# Drivers.net
KiCad netlist of a schematic drawn in Altium Designer
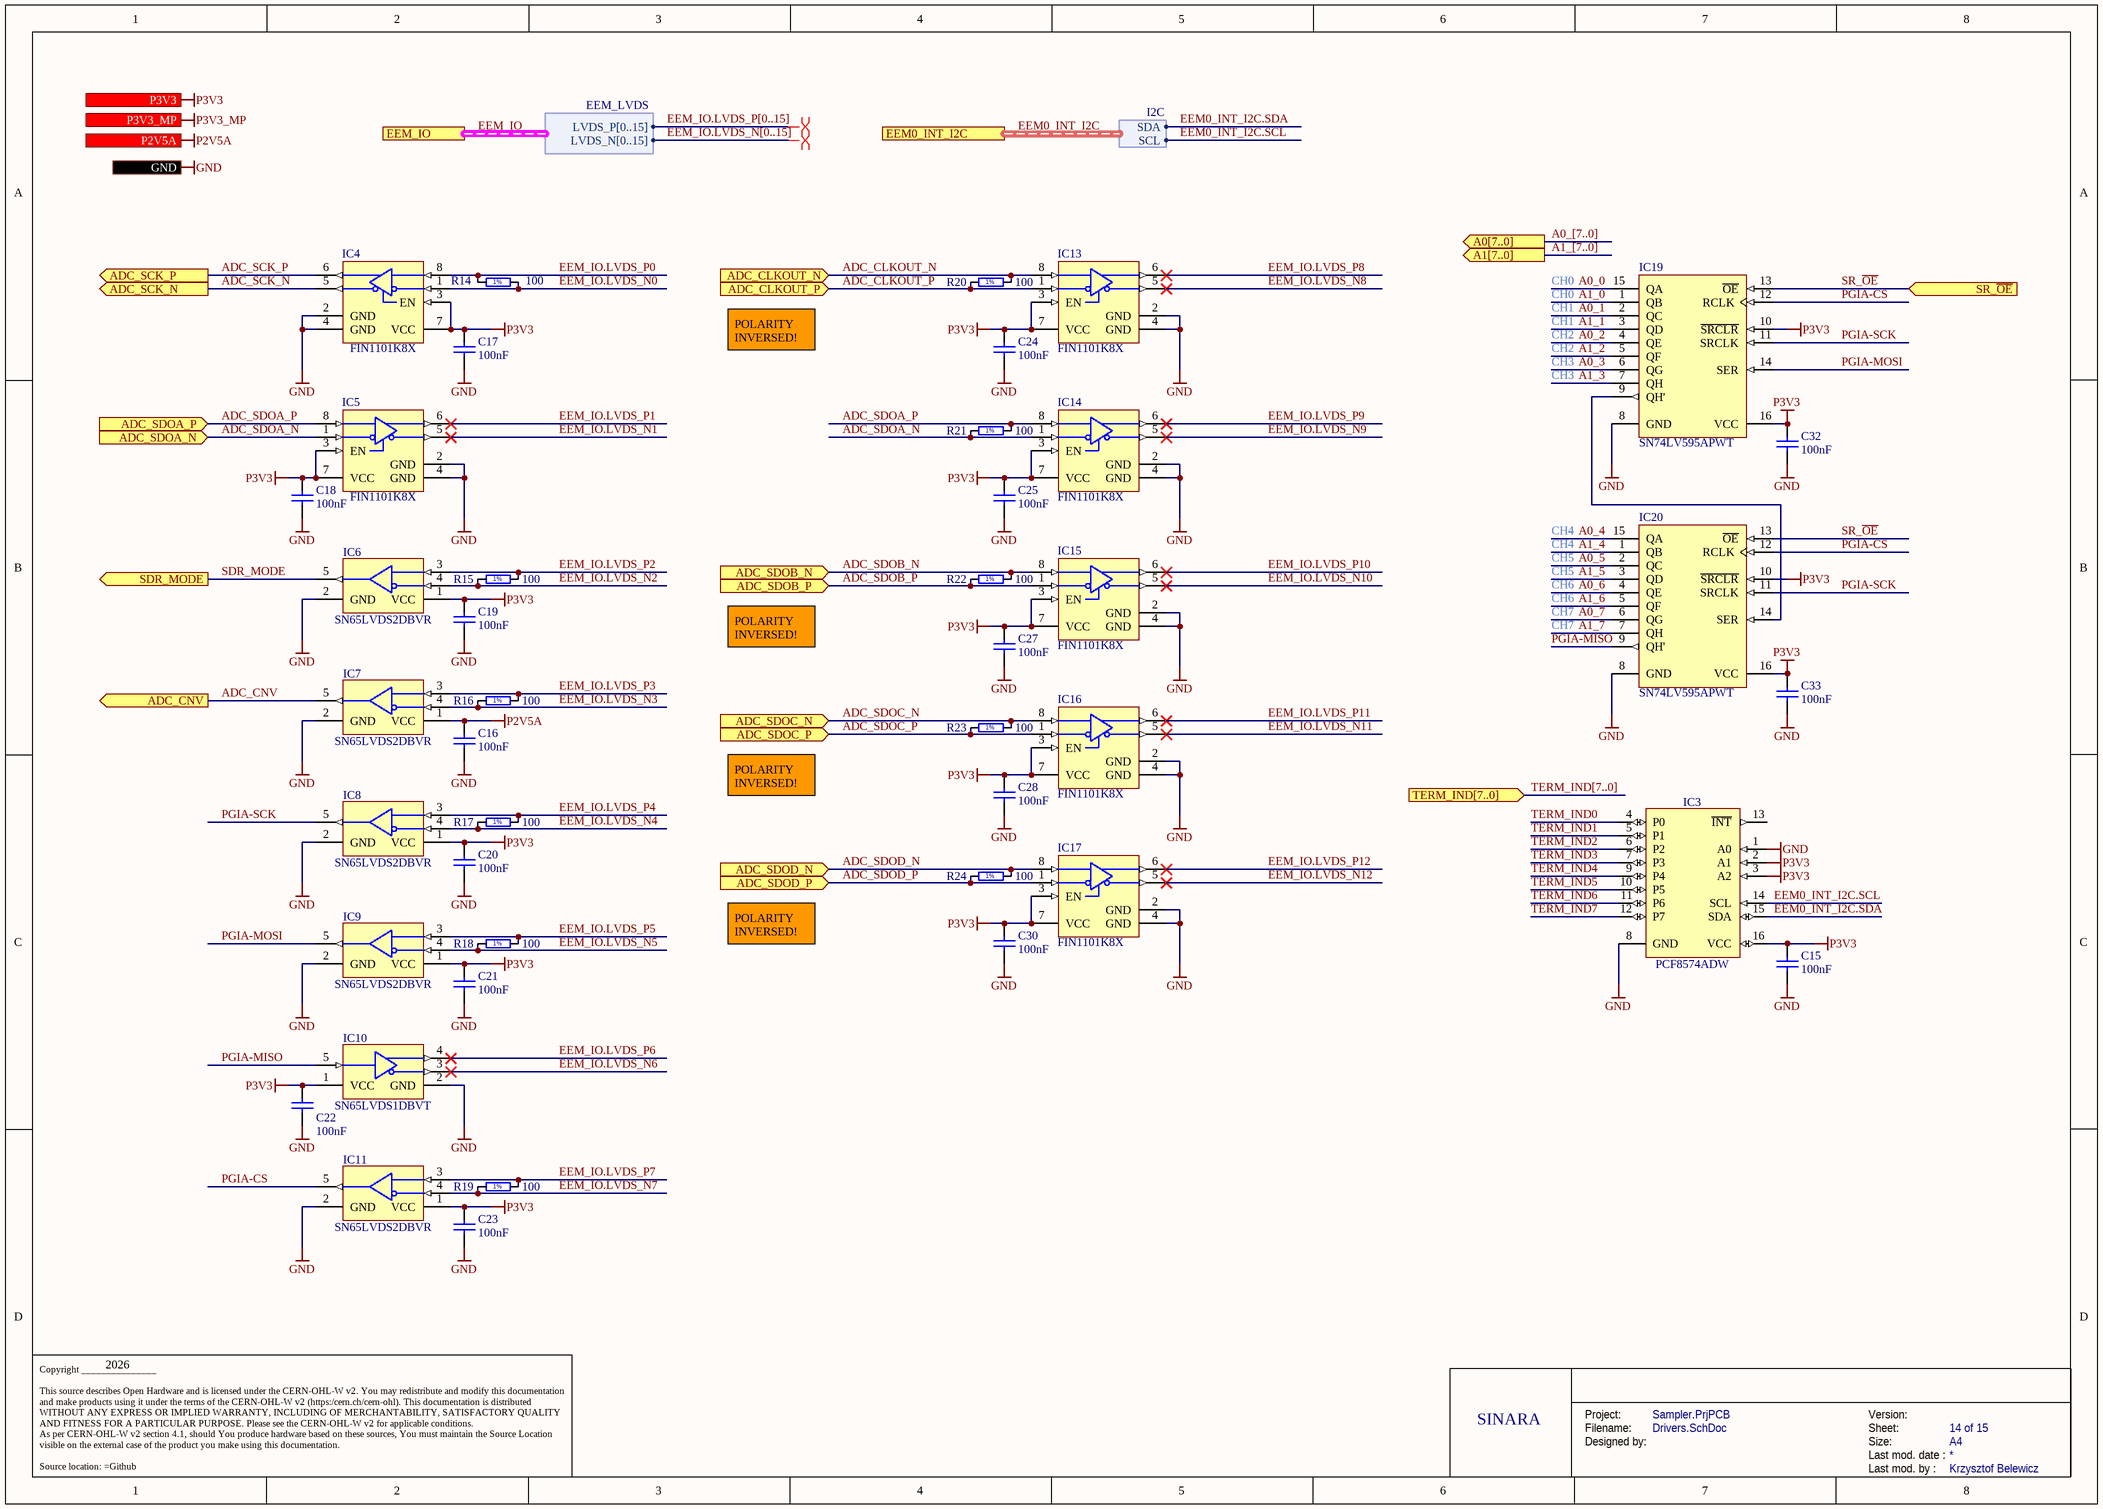
[diagram p0: Drivers.SchDoc]

(export (version "E")
  (design (tool "Eeschema 10.0.6"))
  (components
    (comp (ref "C15")
      (value "100nF")
      (footprint "CAPC1005X55N")
      (description "Non-polarised capacitor")
      (fields
        (field (name "PART NUMBER") "CC0402_100NF_50V_10%_X7R")
        (field (name "VOLTAGE") "50V")
        (field (name "AUTHOR") "CERN DEM MR")
      )
      (libsource (lib "Capacitors") (part "Capacitor - non polarized"))
    )
    (comp (ref "C16")
      (value "100nF")
      (footprint "CAPC1005X55N")
      (description "Non-polarised capacitor")
      (fields
        (field (name "PART NUMBER") "CC0402_100NF_50V_10%_X7R")
        (field (name "VOLTAGE") "50V")
        (field (name "AUTHOR") "CERN DEM MR")
      )
      (libsource (lib "Capacitors") (part "Capacitor - non polarized"))
    )
    (comp (ref "C17")
      (value "100nF")
      (footprint "CAPC1005X55N")
      (description "Non-polarised capacitor")
      (fields
        (field (name "PART NUMBER") "CC0402_100NF_50V_10%_X7R")
        (field (name "VOLTAGE") "50V")
        (field (name "AUTHOR") "CERN DEM MR")
      )
      (libsource (lib "Capacitors") (part "Capacitor - non polarized"))
    )
    (comp (ref "C18")
      (value "100nF")
      (footprint "CAPC1005X55N")
      (description "Non-polarised capacitor")
      (fields
        (field (name "PART NUMBER") "CC0402_100NF_50V_10%_X7R")
        (field (name "VOLTAGE") "50V")
        (field (name "AUTHOR") "CERN DEM MR")
      )
      (libsource (lib "Capacitors") (part "Capacitor - non polarized"))
    )
    (comp (ref "C19")
      (value "100nF")
      (footprint "CAPC1005X55N")
      (description "Non-polarised capacitor")
      (fields
        (field (name "PART NUMBER") "CC0402_100NF_50V_10%_X7R")
        (field (name "VOLTAGE") "50V")
        (field (name "AUTHOR") "CERN DEM MR")
      )
      (libsource (lib "Capacitors") (part "Capacitor - non polarized"))
    )
    (comp (ref "C20")
      (value "100nF")
      (footprint "CAPC1005X55N")
      (description "Non-polarised capacitor")
      (fields
        (field (name "PART NUMBER") "CC0402_100NF_50V_10%_X7R")
        (field (name "VOLTAGE") "50V")
        (field (name "AUTHOR") "CERN DEM MR")
      )
      (libsource (lib "Capacitors") (part "Capacitor - non polarized"))
    )
    (comp (ref "C21")
      (value "100nF")
      (footprint "CAPC1005X55N")
      (description "Non-polarised capacitor")
      (fields
        (field (name "PART NUMBER") "CC0402_100NF_50V_10%_X7R")
        (field (name "VOLTAGE") "50V")
        (field (name "AUTHOR") "CERN DEM MR")
      )
      (libsource (lib "Capacitors") (part "Capacitor - non polarized"))
    )
    (comp (ref "C22")
      (value "100nF")
      (footprint "CAPC1005X55N")
      (description "Non-polarised capacitor")
      (fields
        (field (name "PART NUMBER") "CC0402_100NF_50V_10%_X7R")
        (field (name "VOLTAGE") "50V")
        (field (name "AUTHOR") "CERN DEM MR")
      )
      (libsource (lib "Capacitors") (part "Capacitor - non polarized"))
    )
    (comp (ref "C23")
      (value "100nF")
      (footprint "CAPC1005X55N")
      (description "Non-polarised capacitor")
      (fields
        (field (name "PART NUMBER") "CC0402_100NF_50V_10%_X7R")
        (field (name "VOLTAGE") "50V")
        (field (name "AUTHOR") "CERN DEM MR")
      )
      (libsource (lib "Capacitors") (part "Capacitor - non polarized"))
    )
    (comp (ref "C24")
      (value "100nF")
      (footprint "CAPC1005X55N")
      (description "Non-polarised capacitor")
      (fields
        (field (name "PART NUMBER") "CC0402_100NF_50V_10%_X7R")
        (field (name "VOLTAGE") "50V")
        (field (name "AUTHOR") "CERN DEM MR")
      )
      (libsource (lib "Capacitors") (part "Capacitor - non polarized"))
    )
    (comp (ref "C25")
      (value "100nF")
      (footprint "CAPC1005X55N")
      (description "Non-polarised capacitor")
      (fields
        (field (name "PART NUMBER") "CC0402_100NF_50V_10%_X7R")
        (field (name "VOLTAGE") "50V")
        (field (name "AUTHOR") "CERN DEM MR")
      )
      (libsource (lib "Capacitors") (part "Capacitor - non polarized"))
    )
    (comp (ref "C27")
      (value "100nF")
      (footprint "CAPC1005X55N")
      (description "Non-polarised capacitor")
      (fields
        (field (name "PART NUMBER") "CC0402_100NF_50V_10%_X7R")
        (field (name "VOLTAGE") "50V")
        (field (name "AUTHOR") "CERN DEM MR")
      )
      (libsource (lib "Capacitors") (part "Capacitor - non polarized"))
    )
    (comp (ref "C28")
      (value "100nF")
      (footprint "CAPC1005X55N")
      (description "Non-polarised capacitor")
      (fields
        (field (name "PART NUMBER") "CC0402_100NF_50V_10%_X7R")
        (field (name "VOLTAGE") "50V")
        (field (name "AUTHOR") "CERN DEM MR")
      )
      (libsource (lib "Capacitors") (part "Capacitor - non polarized"))
    )
    (comp (ref "C30")
      (value "100nF")
      (footprint "CAPC1005X55N")
      (description "Non-polarised capacitor")
      (fields
        (field (name "PART NUMBER") "CC0402_100NF_50V_10%_X7R")
        (field (name "VOLTAGE") "50V")
        (field (name "AUTHOR") "CERN DEM MR")
      )
      (libsource (lib "Capacitors") (part "Capacitor - non polarized"))
    )
    (comp (ref "C32")
      (value "100nF")
      (footprint "CAPC1005X55N")
      (description "Non-polarised capacitor")
      (fields
        (field (name "PART NUMBER") "CC0402_100NF_50V_10%_X7R")
        (field (name "VOLTAGE") "50V")
        (field (name "AUTHOR") "CERN DEM MR")
      )
      (libsource (lib "Capacitors") (part "Capacitor - non polarized"))
    )
    (comp (ref "C33")
      (value "100nF")
      (footprint "CAPC1005X55N")
      (description "Non-polarised capacitor")
      (fields
        (field (name "PART NUMBER") "CC0402_100NF_50V_10%_X7R")
        (field (name "VOLTAGE") "50V")
        (field (name "AUTHOR") "CERN DEM MR")
      )
      (libsource (lib "Capacitors") (part "Capacitor - non polarized"))
    )
    (comp (ref "IC3")
      (value "PCF8574ADW")
      (footprint "SOIC127P1030X265-16N")
      (description "Remote 8-bit I/O Expander For I2C Bus")
      (fields (field (name "MANUFACTURER") "TEXAS INSTRUMENTS") (field (name "AUTHOR") "CERN DEM JLC"))
      (libsource (lib "ICs And Semiconductors") (part "PCF8574ADW"))
    )
    (comp (ref "IC4")
      (value "FIN1101K8X")
      (footprint "SOP50P310X90-8N")
      (description "LVDS Single Port High Speed Repeater")
      (fields (field (name "MANUFACTURER") "FAIRCHILD SEMICONDUCTOR") (field (name "AUTHOR") "CERN DEM JLC"))
      (libsource (lib "") (part "FIN1101K8X_1"))
    )
    (comp (ref "IC5")
      (value "FIN1101K8X")
      (footprint "SOP50P310X90-8N")
      (description "LVDS Single Port High Speed Repeater")
      (fields (field (name "MANUFACTURER") "FAIRCHILD SEMICONDUCTOR") (field (name "AUTHOR") "CERN DEM JLC"))
      (libsource (lib "ICs And Semiconductors") (part "FIN1101K8X"))
    )
    (comp (ref "IC6")
      (value "SN65LVDS2DBVR")
      (footprint "SOT95P280X145-5N")
      (description "High-Speed Differential Line Receiver")
      (fields (field (name "MANUFACTURER") "TEXAS INSTRUMENTS") (field (name "AUTHOR") "CERN DEM JLC"))
      (libsource (lib "ICs And Semiconductors") (part "SN65LVDS2DBV"))
    )
    (comp (ref "IC7")
      (value "SN65LVDS2DBVR")
      (footprint "SOT95P280X145-5N")
      (description "High-Speed Differential Line Receiver")
      (fields (field (name "MANUFACTURER") "TEXAS INSTRUMENTS") (field (name "AUTHOR") "CERN DEM JLC"))
      (libsource (lib "ICs And Semiconductors") (part "SN65LVDS2DBV"))
    )
    (comp (ref "IC8")
      (value "SN65LVDS2DBVR")
      (footprint "SOT95P280X145-5N")
      (description "High-Speed Differential Line Receiver")
      (fields (field (name "MANUFACTURER") "TEXAS INSTRUMENTS") (field (name "AUTHOR") "CERN DEM JLC"))
      (libsource (lib "ICs And Semiconductors") (part "SN65LVDS2DBV"))
    )
    (comp (ref "IC9")
      (value "SN65LVDS2DBVR")
      (footprint "SOT95P280X145-5N")
      (description "High-Speed Differential Line Receiver")
      (fields (field (name "MANUFACTURER") "TEXAS INSTRUMENTS") (field (name "AUTHOR") "CERN DEM JLC"))
      (libsource (lib "ICs And Semiconductors") (part "SN65LVDS2DBV"))
    )
    (comp (ref "IC10")
      (value "SN65LVDS1DBVT")
      (footprint "SOT95P280X145-5N")
      (description "High-Speed Differential Line Driver")
      (fields (field (name "MANUFACTURER") "TEXAS INSTRUMENTS") (field (name "AUTHOR") "CERN DEM JLC"))
      (libsource (lib "ICs And Semiconductors") (part "SN65LVDS1DBV"))
    )
    (comp (ref "IC11")
      (value "SN65LVDS2DBVR")
      (footprint "SOT95P280X145-5N")
      (description "High-Speed Differential Line Receiver")
      (fields (field (name "MANUFACTURER") "TEXAS INSTRUMENTS") (field (name "AUTHOR") "CERN DEM JLC"))
      (libsource (lib "ICs And Semiconductors") (part "SN65LVDS2DBV"))
    )
    (comp (ref "IC13")
      (value "FIN1101K8X")
      (footprint "SOP50P310X90-8N")
      (description "LVDS Single Port High Speed Repeater")
      (fields (field (name "MANUFACTURER") "FAIRCHILD SEMICONDUCTOR") (field (name "AUTHOR") "CERN DEM JLC"))
      (libsource (lib "ICs And Semiconductors") (part "FIN1101K8X"))
    )
    (comp (ref "IC14")
      (value "FIN1101K8X")
      (footprint "SOP50P310X90-8N")
      (description "LVDS Single Port High Speed Repeater")
      (fields (field (name "MANUFACTURER") "FAIRCHILD SEMICONDUCTOR") (field (name "AUTHOR") "CERN DEM JLC"))
      (libsource (lib "ICs And Semiconductors") (part "FIN1101K8X"))
    )
    (comp (ref "IC15")
      (value "FIN1101K8X")
      (footprint "SOP50P310X90-8N")
      (description "LVDS Single Port High Speed Repeater")
      (fields (field (name "MANUFACTURER") "FAIRCHILD SEMICONDUCTOR") (field (name "AUTHOR") "CERN DEM JLC"))
      (libsource (lib "ICs And Semiconductors") (part "FIN1101K8X"))
    )
    (comp (ref "IC16")
      (value "FIN1101K8X")
      (footprint "SOP50P310X90-8N")
      (description "LVDS Single Port High Speed Repeater")
      (fields (field (name "MANUFACTURER") "FAIRCHILD SEMICONDUCTOR") (field (name "AUTHOR") "CERN DEM JLC"))
      (libsource (lib "ICs And Semiconductors") (part "FIN1101K8X"))
    )
    (comp (ref "IC17")
      (value "FIN1101K8X")
      (footprint "SOP50P310X90-8N")
      (description "LVDS Single Port High Speed Repeater")
      (fields (field (name "MANUFACTURER") "FAIRCHILD SEMICONDUCTOR") (field (name "AUTHOR") "CERN DEM JLC"))
      (libsource (lib "ICs And Semiconductors") (part "FIN1101K8X"))
    )
    (comp (ref "IC19")
      (value "SN74LV595APWT")
      (footprint "SOP65P640X120-16N")
      (description "8-Bit Shift Register With 3-State Output Register")
      (fields (field (name "MANUFACTURER") "TEXAS INSTRUMENTS") (field (name "AUTHOR") "CERN DEM JLC"))
      (libsource (lib "ICs And Semiconductors") (part "74595"))
    )
    (comp (ref "IC20")
      (value "SN74LV595APWT")
      (footprint "SOP65P640X120-16N")
      (description "8-Bit Shift Register With 3-State Output Register")
      (fields (field (name "MANUFACTURER") "TEXAS INSTRUMENTS") (field (name "AUTHOR") "CERN DEM JLC"))
      (libsource (lib "ICs And Semiconductors") (part "74595"))
    )
    (comp (ref "R14")
      (value "100")
      (footprint "RESC1005X40N")
      (description "Resistor - 1%")
      (fields
        (field (name "PART NUMBER") "R0402_100R_1%_0.1W_100PPM")
        (field (name "POWER") "0.1W")
        (field (name "AUTHOR") "CERN DEM JLC")
      )
      (libsource (lib "Resistors") (part "Resistor - 1%"))
    )
    (comp (ref "R15")
      (value "100")
      (footprint "RESC1005X40N")
      (description "Resistor - 1%")
      (fields
        (field (name "PART NUMBER") "R0402_100R_1%_0.1W_100PPM")
        (field (name "POWER") "0.1W")
        (field (name "AUTHOR") "CERN DEM JLC")
      )
      (libsource (lib "Resistors") (part "Resistor - 1%"))
    )
    (comp (ref "R16")
      (value "100")
      (footprint "RESC1005X40N")
      (description "Resistor - 1%")
      (fields
        (field (name "PART NUMBER") "R0402_100R_1%_0.1W_100PPM")
        (field (name "POWER") "0.1W")
        (field (name "AUTHOR") "CERN DEM JLC")
      )
      (libsource (lib "Resistors") (part "Resistor - 1%"))
    )
    (comp (ref "R17")
      (value "100")
      (footprint "RESC1005X40N")
      (description "Resistor - 1%")
      (fields
        (field (name "PART NUMBER") "R0402_100R_1%_0.1W_100PPM")
        (field (name "POWER") "0.1W")
        (field (name "AUTHOR") "CERN DEM JLC")
      )
      (libsource (lib "Resistors") (part "Resistor - 1%"))
    )
    (comp (ref "R18")
      (value "100")
      (footprint "RESC1005X40N")
      (description "Resistor - 1%")
      (fields
        (field (name "PART NUMBER") "R0402_100R_1%_0.1W_100PPM")
        (field (name "POWER") "0.1W")
        (field (name "AUTHOR") "CERN DEM JLC")
      )
      (libsource (lib "Resistors") (part "Resistor - 1%"))
    )
    (comp (ref "R19")
      (value "100")
      (footprint "RESC1005X40N")
      (description "Resistor - 1%")
      (fields
        (field (name "PART NUMBER") "R0402_100R_1%_0.1W_100PPM")
        (field (name "POWER") "0.1W")
        (field (name "AUTHOR") "CERN DEM JLC")
      )
      (libsource (lib "Resistors") (part "Resistor - 1%"))
    )
    (comp (ref "R20")
      (value "100")
      (footprint "RESC1005X40N")
      (description "Resistor - 1%")
      (fields
        (field (name "PART NUMBER") "R0402_100R_1%_0.1W_100PPM")
        (field (name "POWER") "0.1W")
        (field (name "AUTHOR") "CERN DEM JLC")
      )
      (libsource (lib "Resistors") (part "Resistor - 1%"))
    )
    (comp (ref "R21")
      (value "100")
      (footprint "RESC1005X40N")
      (description "Resistor - 1%")
      (fields
        (field (name "PART NUMBER") "R0402_100R_1%_0.1W_100PPM")
        (field (name "POWER") "0.1W")
        (field (name "AUTHOR") "CERN DEM JLC")
      )
      (libsource (lib "Resistors") (part "Resistor - 1%"))
    )
    (comp (ref "R22")
      (value "100")
      (footprint "RESC1005X40N")
      (description "Resistor - 1%")
      (fields
        (field (name "PART NUMBER") "R0402_100R_1%_0.1W_100PPM")
        (field (name "POWER") "0.1W")
        (field (name "AUTHOR") "CERN DEM JLC")
      )
      (libsource (lib "Resistors") (part "Resistor - 1%"))
    )
    (comp (ref "R23")
      (value "100")
      (footprint "RESC1005X40N")
      (description "Resistor - 1%")
      (fields
        (field (name "PART NUMBER") "R0402_100R_1%_0.1W_100PPM")
        (field (name "POWER") "0.1W")
        (field (name "AUTHOR") "CERN DEM JLC")
      )
      (libsource (lib "Resistors") (part "Resistor - 1%"))
    )
    (comp (ref "R24")
      (value "100")
      (footprint "RESC1005X40N")
      (description "Resistor - 1%")
      (fields
        (field (name "PART NUMBER") "R0402_100R_1%_0.1W_100PPM")
        (field (name "POWER") "0.1W")
        (field (name "AUTHOR") "CERN DEM JLC")
      )
      (libsource (lib "Resistors") (part "Resistor - 1%"))
    )
  )
  (nets
    (net (code "6") (name "/A0_0") (class "Default")
      (node (ref "IC19") (pin "15") (pinfunction "QA_15") (pintype "tri_state"))
    )
    (net (code "7") (name "/A0_1") (class "Default")
      (node (ref "IC19") (pin "2") (pinfunction "QC_2") (pintype "tri_state"))
    )
    (net (code "8") (name "/A0_2") (class "Default")
      (node (ref "IC19") (pin "4") (pinfunction "QE_4") (pintype "tri_state"))
    )
    (net (code "9") (name "/A0_3") (class "Default")
      (node (ref "IC19") (pin "6") (pinfunction "QG_6") (pintype "tri_state"))
    )
    (net (code "10") (name "/A0_4") (class "Default")
      (node (ref "IC20") (pin "15") (pinfunction "QA_15") (pintype "tri_state"))
    )
    (net (code "11") (name "/A0_5") (class "Default")
      (node (ref "IC20") (pin "2") (pinfunction "QC_2") (pintype "tri_state"))
    )
    (net (code "12") (name "/A0_6") (class "Default")
      (node (ref "IC20") (pin "4") (pinfunction "QE_4") (pintype "tri_state"))
    )
    (net (code "13") (name "/A0_7") (class "Default")
      (node (ref "IC20") (pin "6") (pinfunction "QG_6") (pintype "tri_state"))
    )
    (net (code "15") (name "/A1_0") (class "Default")
      (node (ref "IC19") (pin "1") (pinfunction "QB_1") (pintype "tri_state"))
    )
    (net (code "16") (name "/A1_1") (class "Default")
      (node (ref "IC19") (pin "3") (pinfunction "QD_3") (pintype "tri_state"))
    )
    (net (code "17") (name "/A1_2") (class "Default")
      (node (ref "IC19") (pin "5") (pinfunction "QF_5") (pintype "tri_state"))
    )
    (net (code "18") (name "/A1_3") (class "Default")
      (node (ref "IC19") (pin "7") (pinfunction "QH_7") (pintype "tri_state"))
    )
    (net (code "19") (name "/A1_4") (class "Default")
      (node (ref "IC20") (pin "1") (pinfunction "QB_1") (pintype "tri_state"))
    )
    (net (code "20") (name "/A1_5") (class "Default")
      (node (ref "IC20") (pin "3") (pinfunction "QD_3") (pintype "tri_state"))
    )
    (net (code "21") (name "/A1_6") (class "Default")
      (node (ref "IC20") (pin "5") (pinfunction "QF_5") (pintype "tri_state"))
    )
    (net (code "22") (name "/A1_7") (class "Default")
      (node (ref "IC20") (pin "7") (pinfunction "QH_7") (pintype "tri_state"))
    )
    (net (code "24") (name "/ADC_CLKOUT_N") (class "Default")
      (node (ref "IC13") (pin "8") (pinfunction "RIN+_8") (pintype "input"))
      (node (ref "R20") (pin "2") (pinfunction "2_2") (pintype "passive"))
    )
    (net (code "25") (name "/ADC_CLKOUT_P") (class "Default")
      (node (ref "IC13") (pin "1") (pinfunction "RIN-_1") (pintype "input"))
      (node (ref "R20") (pin "1") (pinfunction "1_1") (pintype "passive"))
    )
    (net (code "26") (name "/ADC_CNV") (class "Default")
      (node (ref "IC7") (pin "5") (pinfunction "R_5") (pintype "output"))
    )
    (net (code "27") (name "/ADC_SCK_N") (class "Default")
      (node (ref "IC4") (pin "5") (pinfunction "DOUT-_5") (pintype "output"))
    )
    (net (code "28") (name "/ADC_SCK_P") (class "Default")
      (node (ref "IC4") (pin "6") (pinfunction "DOUT+_6") (pintype "output"))
    )
    (net (code "29") (name "/ADC_SDOA_N") (class "Default")
      (node (ref "IC14") (pin "1") (pinfunction "RIN-_1") (pintype "input"))
      (node (ref "IC5") (pin "1") (pinfunction "RIN-_1") (pintype "input"))
      (node (ref "R21") (pin "1") (pinfunction "1_1") (pintype "passive"))
    )
    (net (code "30") (name "/ADC_SDOA_P") (class "Default")
      (node (ref "IC14") (pin "8") (pinfunction "RIN+_8") (pintype "input"))
      (node (ref "IC5") (pin "8") (pinfunction "RIN+_8") (pintype "input"))
      (node (ref "R21") (pin "2") (pinfunction "2_2") (pintype "passive"))
    )
    (net (code "31") (name "/ADC_SDOB_N") (class "Default")
      (node (ref "IC15") (pin "8") (pinfunction "RIN+_8") (pintype "input"))
      (node (ref "R22") (pin "2") (pinfunction "2_2") (pintype "passive"))
    )
    (net (code "32") (name "/ADC_SDOB_P") (class "Default")
      (node (ref "IC15") (pin "1") (pinfunction "RIN-_1") (pintype "input"))
      (node (ref "R22") (pin "1") (pinfunction "1_1") (pintype "passive"))
    )
    (net (code "33") (name "/ADC_SDOC_N") (class "Default")
      (node (ref "IC16") (pin "8") (pinfunction "RIN+_8") (pintype "input"))
      (node (ref "R23") (pin "2") (pinfunction "2_2") (pintype "passive"))
    )
    (net (code "34") (name "/ADC_SDOC_P") (class "Default")
      (node (ref "IC16") (pin "1") (pinfunction "RIN-_1") (pintype "input"))
      (node (ref "R23") (pin "1") (pinfunction "1_1") (pintype "passive"))
    )
    (net (code "35") (name "/ADC_SDOD_N") (class "Default")
      (node (ref "IC17") (pin "8") (pinfunction "RIN+_8") (pintype "input"))
      (node (ref "R24") (pin "2") (pinfunction "2_2") (pintype "passive"))
    )
    (net (code "36") (name "/ADC_SDOD_P") (class "Default")
      (node (ref "IC17") (pin "1") (pinfunction "RIN-_1") (pintype "input"))
      (node (ref "R24") (pin "1") (pinfunction "1_1") (pintype "passive"))
    )
    (net (code "37") (name "/EEM0_INT_I2C.SCL") (class "Default")
      (node (ref "IC3") (pin "14") (pinfunction "SCL_14") (pintype "input"))
    )
    (net (code "38") (name "/EEM0_INT_I2C.SDA") (class "Default")
      (node (ref "IC3") (pin "15") (pinfunction "SDA_15") (pintype "bidirectional"))
    )
    (net (code "40") (name "/EEM_IO.LVDS_N0") (class "Default")
      (node (ref "IC4") (pin "1") (pinfunction "RIN-_1") (pintype "input"))
      (node (ref "R14") (pin "1") (pinfunction "1_1") (pintype "passive"))
    )
    (net (code "41") (name "/EEM_IO.LVDS_N1") (class "Default")
      (node (ref "IC5") (pin "5") (pinfunction "DOUT-_5") (pintype "output+no_connect"))
    )
    (net (code "42") (name "/EEM_IO.LVDS_N2") (class "Default")
      (node (ref "IC6") (pin "4") (pinfunction "B_4") (pintype "input"))
      (node (ref "R15") (pin "1") (pinfunction "1_1") (pintype "passive"))
    )
    (net (code "43") (name "/EEM_IO.LVDS_N3") (class "Default")
      (node (ref "IC7") (pin "4") (pinfunction "B_4") (pintype "input"))
      (node (ref "R16") (pin "1") (pinfunction "1_1") (pintype "passive"))
    )
    (net (code "44") (name "/EEM_IO.LVDS_N4") (class "Default")
      (node (ref "IC8") (pin "4") (pinfunction "B_4") (pintype "input"))
      (node (ref "R17") (pin "1") (pinfunction "1_1") (pintype "passive"))
    )
    (net (code "45") (name "/EEM_IO.LVDS_N5") (class "Default")
      (node (ref "IC9") (pin "4") (pinfunction "B_4") (pintype "input"))
      (node (ref "R18") (pin "1") (pinfunction "1_1") (pintype "passive"))
    )
    (net (code "46") (name "/EEM_IO.LVDS_N6") (class "Default")
      (node (ref "IC10") (pin "3") (pinfunction "A_3") (pintype "output+no_connect"))
    )
    (net (code "47") (name "/EEM_IO.LVDS_N7") (class "Default")
      (node (ref "IC11") (pin "4") (pinfunction "B_4") (pintype "input"))
      (node (ref "R19") (pin "1") (pinfunction "1_1") (pintype "passive"))
    )
    (net (code "48") (name "/EEM_IO.LVDS_N8") (class "Default")
      (node (ref "IC13") (pin "5") (pinfunction "DOUT-_5") (pintype "output+no_connect"))
    )
    (net (code "49") (name "/EEM_IO.LVDS_N9") (class "Default")
      (node (ref "IC14") (pin "5") (pinfunction "DOUT-_5") (pintype "output+no_connect"))
    )
    (net (code "50") (name "/EEM_IO.LVDS_N10") (class "Default")
      (node (ref "IC15") (pin "5") (pinfunction "DOUT-_5") (pintype "output+no_connect"))
    )
    (net (code "51") (name "/EEM_IO.LVDS_N11") (class "Default")
      (node (ref "IC16") (pin "5") (pinfunction "DOUT-_5") (pintype "output+no_connect"))
    )
    (net (code "52") (name "/EEM_IO.LVDS_N12") (class "Default")
      (node (ref "IC17") (pin "5") (pinfunction "DOUT-_5") (pintype "output+no_connect"))
    )
    (net (code "53") (name "/EEM_IO.LVDS_P0") (class "Default")
      (node (ref "IC4") (pin "8") (pinfunction "RIN+_8") (pintype "input"))
      (node (ref "R14") (pin "2") (pinfunction "2_2") (pintype "passive"))
    )
    (net (code "54") (name "/EEM_IO.LVDS_P1") (class "Default")
      (node (ref "IC5") (pin "6") (pinfunction "DOUT+_6") (pintype "output+no_connect"))
    )
    (net (code "55") (name "/EEM_IO.LVDS_P2") (class "Default")
      (node (ref "IC6") (pin "3") (pinfunction "A_3") (pintype "input"))
      (node (ref "R15") (pin "2") (pinfunction "2_2") (pintype "passive"))
    )
    (net (code "56") (name "/EEM_IO.LVDS_P3") (class "Default")
      (node (ref "IC7") (pin "3") (pinfunction "A_3") (pintype "input"))
      (node (ref "R16") (pin "2") (pinfunction "2_2") (pintype "passive"))
    )
    (net (code "57") (name "/EEM_IO.LVDS_P4") (class "Default")
      (node (ref "IC8") (pin "3") (pinfunction "A_3") (pintype "input"))
      (node (ref "R17") (pin "2") (pinfunction "2_2") (pintype "passive"))
    )
    (net (code "58") (name "/EEM_IO.LVDS_P5") (class "Default")
      (node (ref "IC9") (pin "3") (pinfunction "A_3") (pintype "input"))
      (node (ref "R18") (pin "2") (pinfunction "2_2") (pintype "passive"))
    )
    (net (code "59") (name "/EEM_IO.LVDS_P6") (class "Default")
      (node (ref "IC10") (pin "4") (pinfunction "B_4") (pintype "output+no_connect"))
    )
    (net (code "60") (name "/EEM_IO.LVDS_P7") (class "Default")
      (node (ref "IC11") (pin "3") (pinfunction "A_3") (pintype "input"))
      (node (ref "R19") (pin "2") (pinfunction "2_2") (pintype "passive"))
    )
    (net (code "61") (name "/EEM_IO.LVDS_P8") (class "Default")
      (node (ref "IC13") (pin "6") (pinfunction "DOUT+_6") (pintype "output+no_connect"))
    )
    (net (code "62") (name "/EEM_IO.LVDS_P9") (class "Default")
      (node (ref "IC14") (pin "6") (pinfunction "DOUT+_6") (pintype "output+no_connect"))
    )
    (net (code "63") (name "/EEM_IO.LVDS_P10") (class "Default")
      (node (ref "IC15") (pin "6") (pinfunction "DOUT+_6") (pintype "output+no_connect"))
    )
    (net (code "64") (name "/EEM_IO.LVDS_P11") (class "Default")
      (node (ref "IC16") (pin "6") (pinfunction "DOUT+_6") (pintype "output+no_connect"))
    )
    (net (code "65") (name "/EEM_IO.LVDS_P12") (class "Default")
      (node (ref "IC17") (pin "6") (pinfunction "DOUT+_6") (pintype "output+no_connect"))
    )
    (net (code "67") (name "/PGIA-CS") (class "Default")
      (node (ref "IC11") (pin "5") (pinfunction "R_5") (pintype "output"))
      (node (ref "IC19") (pin "12") (pinfunction "RCLK_12") (pintype "input"))
      (node (ref "IC20") (pin "12") (pinfunction "RCLK_12") (pintype "input"))
    )
    (net (code "68") (name "/PGIA-MISO") (class "Default")
      (node (ref "IC10") (pin "5") (pinfunction "R_5") (pintype "input"))
      (node (ref "IC20") (pin "9") (pinfunction "QH'_9") (pintype "output"))
    )
    (net (code "69") (name "/PGIA-MOSI") (class "Default")
      (node (ref "IC19") (pin "14") (pinfunction "SER_14") (pintype "input"))
      (node (ref "IC9") (pin "5") (pinfunction "R_5") (pintype "output"))
    )
    (net (code "70") (name "/PGIA-SCK") (class "Default")
      (node (ref "IC19") (pin "11") (pinfunction "SRCLK_11") (pintype "input"))
      (node (ref "IC20") (pin "11") (pinfunction "SRCLK_11") (pintype "input"))
      (node (ref "IC8") (pin "5") (pinfunction "R_5") (pintype "output"))
    )
    (net (code "71") (name "/SDR_MODE") (class "Default")
      (node (ref "IC6") (pin "5") (pinfunction "R_5") (pintype "output"))
    )
    (net (code "72") (name "/SR_~{OE}") (class "Default")
      (node (ref "IC19") (pin "13") (pinfunction "~{OE}_13") (pintype "input"))
      (node (ref "IC20") (pin "13") (pinfunction "~{OE}_13") (pintype "input"))
    )
    (net (code "73") (name "/TERM_IND0") (class "Default")
      (node (ref "IC3") (pin "4") (pinfunction "P0_4") (pintype "bidirectional"))
    )
    (net (code "74") (name "/TERM_IND1") (class "Default")
      (node (ref "IC3") (pin "5") (pinfunction "P1_5") (pintype "bidirectional"))
    )
    (net (code "75") (name "/TERM_IND2") (class "Default")
      (node (ref "IC3") (pin "6") (pinfunction "P2_6") (pintype "bidirectional"))
    )
    (net (code "76") (name "/TERM_IND3") (class "Default")
      (node (ref "IC3") (pin "7") (pinfunction "P3_7") (pintype "bidirectional"))
    )
    (net (code "77") (name "/TERM_IND4") (class "Default")
      (node (ref "IC3") (pin "9") (pinfunction "P4_9") (pintype "bidirectional"))
    )
    (net (code "78") (name "/TERM_IND5") (class "Default")
      (node (ref "IC3") (pin "10") (pinfunction "P5_10") (pintype "bidirectional"))
    )
    (net (code "79") (name "/TERM_IND6") (class "Default")
      (node (ref "IC3") (pin "11") (pinfunction "P6_11") (pintype "bidirectional"))
    )
    (net (code "80") (name "/TERM_IND7") (class "Default")
      (node (ref "IC3") (pin "12") (pinfunction "P7_12") (pintype "bidirectional"))
    )
    (net (code "83") (name "GND") (class "Default")
      (node (ref "C15") (pin "1") (pinfunction "1_1") (pintype "passive"))
      (node (ref "C16") (pin "1") (pinfunction "1_1") (pintype "passive"))
      (node (ref "C17") (pin "1") (pinfunction "1_1") (pintype "passive"))
      (node (ref "C18") (pin "1") (pinfunction "1_1") (pintype "passive"))
      (node (ref "C19") (pin "1") (pinfunction "1_1") (pintype "passive"))
      (node (ref "C20") (pin "1") (pinfunction "1_1") (pintype "passive"))
      (node (ref "C21") (pin "1") (pinfunction "1_1") (pintype "passive"))
      (node (ref "C22") (pin "1") (pinfunction "1_1") (pintype "passive"))
      (node (ref "C23") (pin "1") (pinfunction "1_1") (pintype "passive"))
      (node (ref "C24") (pin "1") (pinfunction "1_1") (pintype "passive"))
      (node (ref "C25") (pin "1") (pinfunction "1_1") (pintype "passive"))
      (node (ref "C27") (pin "1") (pinfunction "1_1") (pintype "passive"))
      (node (ref "C28") (pin "1") (pinfunction "1_1") (pintype "passive"))
      (node (ref "C30") (pin "1") (pinfunction "1_1") (pintype "passive"))
      (node (ref "C32") (pin "1") (pinfunction "1_1") (pintype "passive"))
      (node (ref "C33") (pin "1") (pinfunction "1_1") (pintype "passive"))
      (node (ref "IC10") (pin "2") (pinfunction "GND_2") (pintype "power_in"))
      (node (ref "IC11") (pin "2") (pinfunction "GND_2") (pintype "power_in"))
      (node (ref "IC13") (pin "2") (pinfunction "GND_2") (pintype "power_in"))
      (node (ref "IC13") (pin "4") (pinfunction "GND_4") (pintype "power_in"))
      (node (ref "IC14") (pin "2") (pinfunction "GND_2") (pintype "power_in"))
      (node (ref "IC14") (pin "4") (pinfunction "GND_4") (pintype "power_in"))
      (node (ref "IC15") (pin "2") (pinfunction "GND_2") (pintype "power_in"))
      (node (ref "IC15") (pin "4") (pinfunction "GND_4") (pintype "power_in"))
      (node (ref "IC16") (pin "2") (pinfunction "GND_2") (pintype "power_in"))
      (node (ref "IC16") (pin "4") (pinfunction "GND_4") (pintype "power_in"))
      (node (ref "IC17") (pin "2") (pinfunction "GND_2") (pintype "power_in"))
      (node (ref "IC17") (pin "4") (pinfunction "GND_4") (pintype "power_in"))
      (node (ref "IC19") (pin "8") (pinfunction "GND_8") (pintype "power_in"))
      (node (ref "IC20") (pin "8") (pinfunction "GND_8") (pintype "power_in"))
      (node (ref "IC3") (pin "1") (pinfunction "A0_1") (pintype "input"))
      (node (ref "IC3") (pin "8") (pinfunction "GND_8") (pintype "power_in"))
      (node (ref "IC4") (pin "2") (pinfunction "GND_2") (pintype "power_in"))
      (node (ref "IC4") (pin "4") (pinfunction "GND_4") (pintype "power_in"))
      (node (ref "IC5") (pin "2") (pinfunction "GND_2") (pintype "power_in"))
      (node (ref "IC5") (pin "4") (pinfunction "GND_4") (pintype "power_in"))
      (node (ref "IC6") (pin "2") (pinfunction "GND_2") (pintype "power_in"))
      (node (ref "IC7") (pin "2") (pinfunction "GND_2") (pintype "power_in"))
      (node (ref "IC8") (pin "2") (pinfunction "GND_2") (pintype "power_in"))
      (node (ref "IC9") (pin "2") (pinfunction "GND_2") (pintype "power_in"))
    )
    (net (code "84") (name "Net-(IC19-QH')") (class "Default")
      (node (ref "IC19") (pin "9") (pinfunction "QH'_9") (pintype "output"))
      (node (ref "IC20") (pin "14") (pinfunction "SER_14") (pintype "input"))
    )
    (net (code "85") (name "P2V5A") (class "Default")
      (node (ref "C16") (pin "2") (pinfunction "2_2") (pintype "passive"))
      (node (ref "IC7") (pin "1") (pinfunction "VCC_1") (pintype "power_in"))
    )
    (net (code "86") (name "P3V3") (class "Default")
      (node (ref "C15") (pin "2") (pinfunction "2_2") (pintype "passive"))
      (node (ref "C17") (pin "2") (pinfunction "2_2") (pintype "passive"))
      (node (ref "C18") (pin "2") (pinfunction "2_2") (pintype "passive"))
      (node (ref "C19") (pin "2") (pinfunction "2_2") (pintype "passive"))
      (node (ref "C20") (pin "2") (pinfunction "2_2") (pintype "passive"))
      (node (ref "C21") (pin "2") (pinfunction "2_2") (pintype "passive"))
      (node (ref "C22") (pin "2") (pinfunction "2_2") (pintype "passive"))
      (node (ref "C23") (pin "2") (pinfunction "2_2") (pintype "passive"))
      (node (ref "C24") (pin "2") (pinfunction "2_2") (pintype "passive"))
      (node (ref "C25") (pin "2") (pinfunction "2_2") (pintype "passive"))
      (node (ref "C27") (pin "2") (pinfunction "2_2") (pintype "passive"))
      (node (ref "C28") (pin "2") (pinfunction "2_2") (pintype "passive"))
      (node (ref "C30") (pin "2") (pinfunction "2_2") (pintype "passive"))
      (node (ref "C32") (pin "2") (pinfunction "2_2") (pintype "passive"))
      (node (ref "C33") (pin "2") (pinfunction "2_2") (pintype "passive"))
      (node (ref "IC10") (pin "1") (pinfunction "VCC_1") (pintype "power_in"))
      (node (ref "IC11") (pin "1") (pinfunction "VCC_1") (pintype "power_in"))
      (node (ref "IC13") (pin "3") (pinfunction "EN_3") (pintype "input"))
      (node (ref "IC13") (pin "7") (pinfunction "VCC_7") (pintype "power_in"))
      (node (ref "IC14") (pin "3") (pinfunction "EN_3") (pintype "input"))
      (node (ref "IC14") (pin "7") (pinfunction "VCC_7") (pintype "power_in"))
      (node (ref "IC15") (pin "3") (pinfunction "EN_3") (pintype "input"))
      (node (ref "IC15") (pin "7") (pinfunction "VCC_7") (pintype "power_in"))
      (node (ref "IC16") (pin "3") (pinfunction "EN_3") (pintype "input"))
      (node (ref "IC16") (pin "7") (pinfunction "VCC_7") (pintype "power_in"))
      (node (ref "IC17") (pin "3") (pinfunction "EN_3") (pintype "input"))
      (node (ref "IC17") (pin "7") (pinfunction "VCC_7") (pintype "power_in"))
      (node (ref "IC19") (pin "10") (pinfunction "~{SRCLR}_10") (pintype "input"))
      (node (ref "IC19") (pin "16") (pinfunction "VCC_16") (pintype "power_in"))
      (node (ref "IC20") (pin "10") (pinfunction "~{SRCLR}_10") (pintype "input"))
      (node (ref "IC20") (pin "16") (pinfunction "VCC_16") (pintype "power_in"))
      (node (ref "IC3") (pin "16") (pinfunction "VCC_16") (pintype "bidirectional"))
      (node (ref "IC3") (pin "2") (pinfunction "A1_2") (pintype "input"))
      (node (ref "IC3") (pin "3") (pinfunction "A2_3") (pintype "input"))
      (node (ref "IC4") (pin "3") (pinfunction "EN_3") (pintype "input"))
      (node (ref "IC4") (pin "7") (pinfunction "VCC_7") (pintype "power_in"))
      (node (ref "IC5") (pin "3") (pinfunction "EN_3") (pintype "input"))
      (node (ref "IC5") (pin "7") (pinfunction "VCC_7") (pintype "power_in"))
      (node (ref "IC6") (pin "1") (pinfunction "VCC_1") (pintype "power_in"))
      (node (ref "IC8") (pin "1") (pinfunction "VCC_1") (pintype "power_in"))
      (node (ref "IC9") (pin "1") (pinfunction "VCC_1") (pintype "power_in"))
    )
    (net (code "88") (name "unconnected-(IC3-~{INT}-Pad13)") (class "Default")
      (node (ref "IC3") (pin "13") (pinfunction "~{INT}_13") (pintype "output"))
    )
  )
)
